# rev1.net
KiCad netlist of a schematic drawn in EAGLE
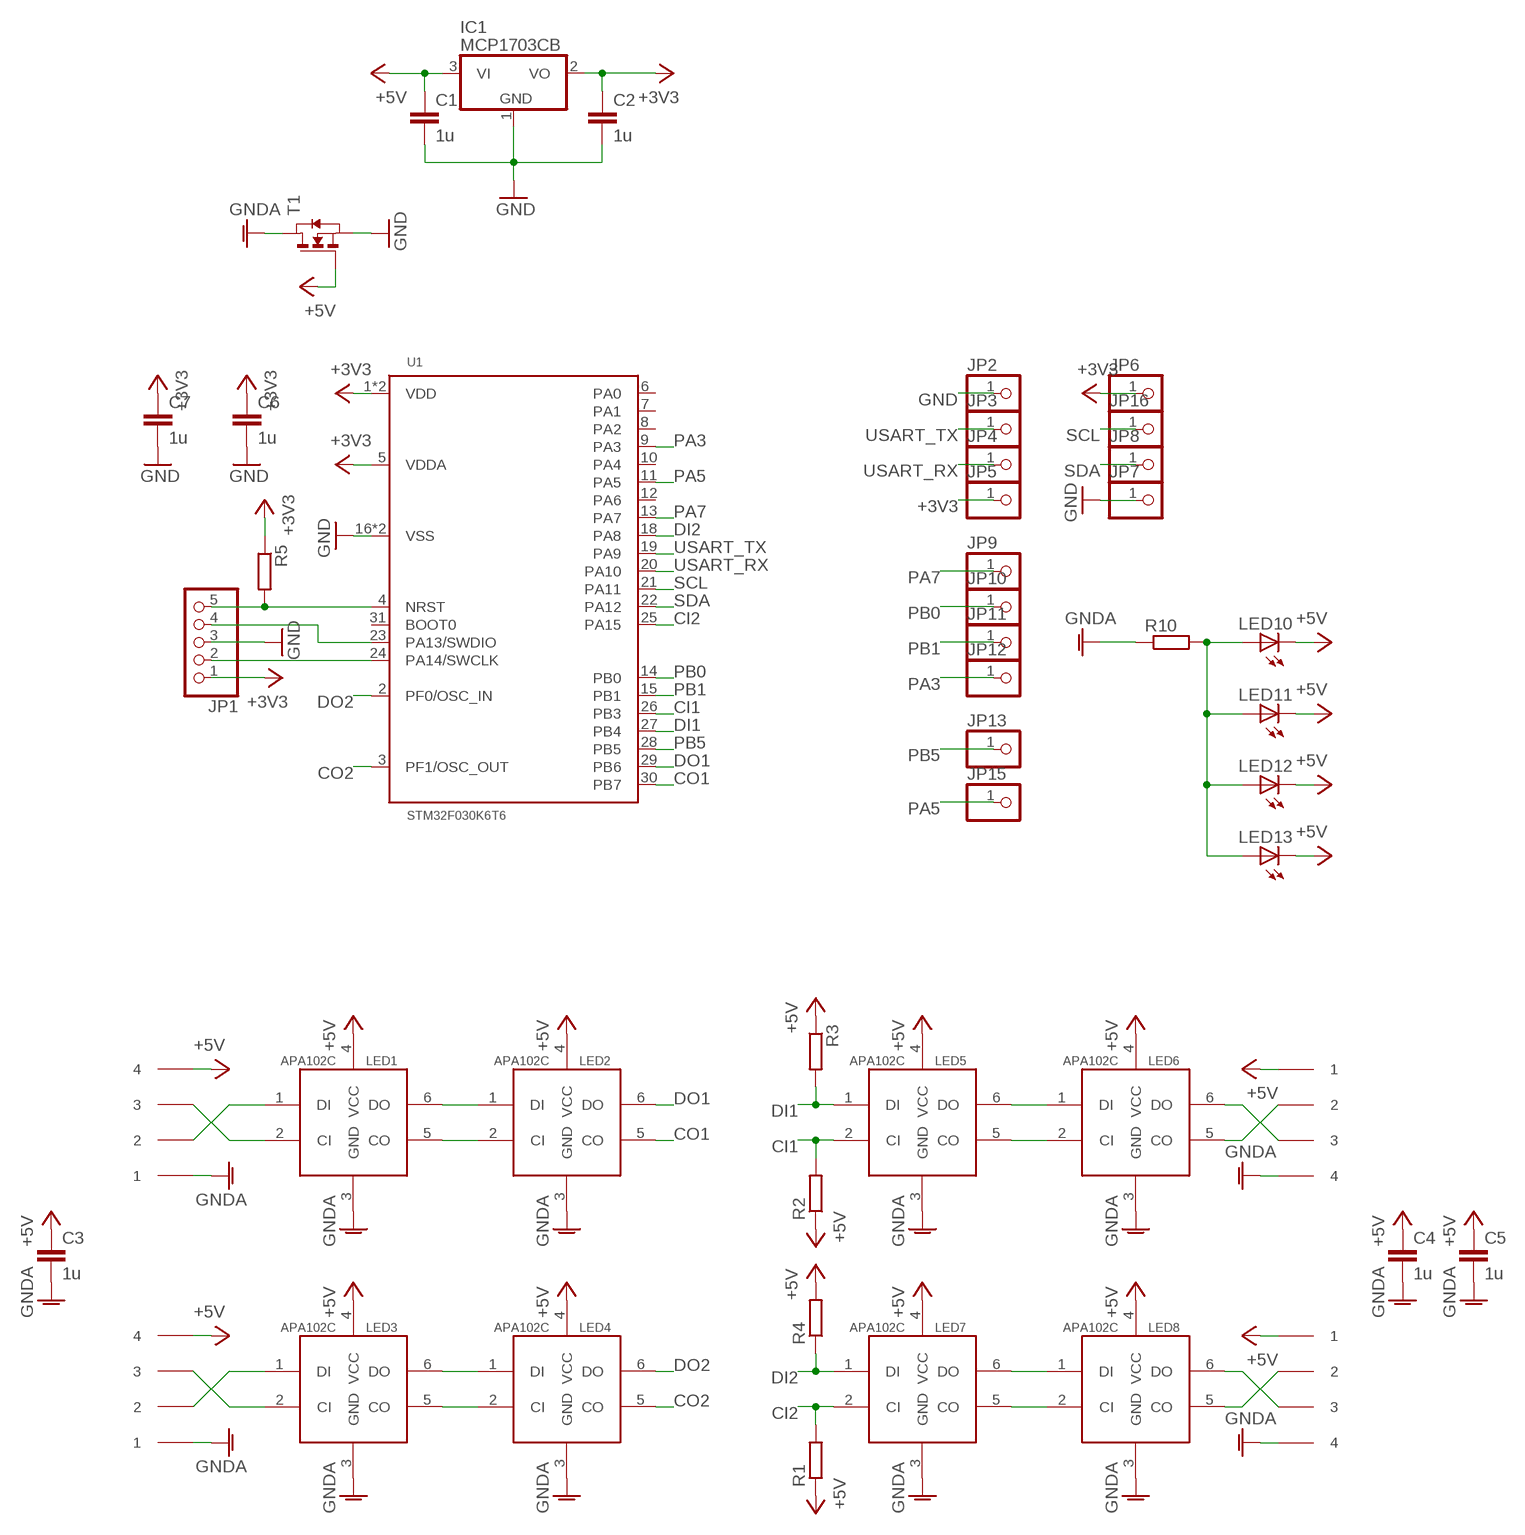
[diagram p0: schematic, sheet 1]

(export (version "E")
  (design (tool "Eeschema 10.0.6"))
  (components
    (comp (ref "C1")
      (value "1u")
      (footprint "eagle-import:C0603")
      (libsource (lib "eagle-import") (part "CC0603"))
    )
    (comp (ref "C2")
      (value "1u")
      (footprint "eagle-import:C0603")
      (libsource (lib "eagle-import") (part "CC0603"))
    )
    (comp (ref "C3")
      (value "1u")
      (footprint "eagle-import:C0603")
      (libsource (lib "eagle-import") (part "CC0603"))
    )
    (comp (ref "C4")
      (value "1u")
      (footprint "eagle-import:C0603")
      (libsource (lib "eagle-import") (part "CC0603"))
    )
    (comp (ref "C5")
      (value "1u")
      (footprint "eagle-import:C0603")
      (libsource (lib "eagle-import") (part "CC0603"))
    )
    (comp (ref "C6")
      (value "1u")
      (footprint "eagle-import:C0603")
      (libsource (lib "eagle-import") (part "CC0603"))
    )
    (comp (ref "C7")
      (value "1u")
      (footprint "eagle-import:C0603")
      (libsource (lib "eagle-import") (part "CC0603"))
    )
    (comp (ref "IC1")
      (value "MCP1703CB")
      (footprint "eagle-import:SOT23")
      (libsource (lib "eagle-import") (part "MCP1703CB"))
    )
    (comp (ref "JP1")
      (value "PINHD-1X5")
      (footprint "eagle-import:1X05")
      (libsource (lib "eagle-import") (part "PINHD-1X5"))
    )
    (comp (ref "JP2")
      (value "PINHD-1X1")
      (footprint "eagle-import:1X01")
      (libsource (lib "eagle-import") (part "PINHD-1X1"))
    )
    (comp (ref "JP3")
      (value "PINHD-1X1")
      (footprint "eagle-import:1X01")
      (libsource (lib "eagle-import") (part "PINHD-1X1"))
    )
    (comp (ref "JP4")
      (value "PINHD-1X1")
      (footprint "eagle-import:1X01")
      (libsource (lib "eagle-import") (part "PINHD-1X1"))
    )
    (comp (ref "JP5")
      (value "PINHD-1X1")
      (footprint "eagle-import:1X01")
      (libsource (lib "eagle-import") (part "PINHD-1X1"))
    )
    (comp (ref "JP6")
      (value "PINHD-1X1")
      (footprint "eagle-import:1X01")
      (libsource (lib "eagle-import") (part "PINHD-1X1"))
    )
    (comp (ref "JP7")
      (value "PINHD-1X1")
      (footprint "eagle-import:1X01")
      (libsource (lib "eagle-import") (part "PINHD-1X1"))
    )
    (comp (ref "JP8")
      (value "PINHD-1X1")
      (footprint "eagle-import:1X01")
      (libsource (lib "eagle-import") (part "PINHD-1X1"))
    )
    (comp (ref "JP9")
      (value "PINHD-1X1")
      (footprint "eagle-import:1X01")
      (libsource (lib "eagle-import") (part "PINHD-1X1"))
    )
    (comp (ref "JP10")
      (value "PINHD-1X1")
      (footprint "eagle-import:1X01")
      (libsource (lib "eagle-import") (part "PINHD-1X1"))
    )
    (comp (ref "JP11")
      (value "PINHD-1X1")
      (footprint "eagle-import:1X01")
      (libsource (lib "eagle-import") (part "PINHD-1X1"))
    )
    (comp (ref "JP12")
      (value "PINHD-1X1")
      (footprint "eagle-import:1X01")
      (libsource (lib "eagle-import") (part "PINHD-1X1"))
    )
    (comp (ref "JP13")
      (value "PINHD-1X1")
      (footprint "eagle-import:1X01")
      (libsource (lib "eagle-import") (part "PINHD-1X1"))
    )
    (comp (ref "JP15")
      (value "PINHD-1X1")
      (footprint "eagle-import:1X01")
      (libsource (lib "eagle-import") (part "PINHD-1X1"))
    )
    (comp (ref "JP16")
      (value "PINHD-1X1")
      (footprint "eagle-import:1X01")
      (libsource (lib "eagle-import") (part "PINHD-1X1"))
    )
    (comp (ref "LED1")
      (value "APA102C")
      (footprint "eagle-import:RGBLED5050")
      (libsource (lib "eagle-import") (part "APA102C"))
    )
    (comp (ref "LED2")
      (value "APA102C")
      (footprint "eagle-import:RGBLED5050")
      (libsource (lib "eagle-import") (part "APA102C"))
    )
    (comp (ref "LED3")
      (value "APA102C")
      (footprint "eagle-import:RGBLED5050")
      (libsource (lib "eagle-import") (part "APA102C"))
    )
    (comp (ref "LED4")
      (value "APA102C")
      (footprint "eagle-import:RGBLED5050")
      (libsource (lib "eagle-import") (part "APA102C"))
    )
    (comp (ref "LED5")
      (value "APA102C")
      (footprint "eagle-import:RGBLED5050")
      (libsource (lib "eagle-import") (part "APA102C"))
    )
    (comp (ref "LED6")
      (value "APA102C")
      (footprint "eagle-import:RGBLED5050")
      (libsource (lib "eagle-import") (part "APA102C"))
    )
    (comp (ref "LED7")
      (value "APA102C")
      (footprint "eagle-import:RGBLED5050")
      (libsource (lib "eagle-import") (part "APA102C"))
    )
    (comp (ref "LED8")
      (value "APA102C")
      (footprint "eagle-import:RGBLED5050")
      (libsource (lib "eagle-import") (part "APA102C"))
    )
    (comp (ref "LED10")
      (value "LEDSML0603")
      (footprint "eagle-import:SML0603")
      (libsource (lib "eagle-import") (part "LEDSML0603"))
    )
    (comp (ref "LED11")
      (value "LEDSML0603")
      (footprint "eagle-import:SML0603")
      (libsource (lib "eagle-import") (part "LEDSML0603"))
    )
    (comp (ref "LED12")
      (value "LEDSML0603")
      (footprint "eagle-import:SML0603")
      (libsource (lib "eagle-import") (part "LEDSML0603"))
    )
    (comp (ref "LED13")
      (value "LEDSML0603")
      (footprint "eagle-import:SML0603")
      (libsource (lib "eagle-import") (part "LEDSML0603"))
    )
    (comp (ref "R1")
      (value "RR0603")
      (footprint "eagle-import:R0603")
      (libsource (lib "eagle-import") (part "RR0603"))
    )
    (comp (ref "R2")
      (value "RR0603")
      (footprint "eagle-import:R0603")
      (libsource (lib "eagle-import") (part "RR0603"))
    )
    (comp (ref "R3")
      (value "RR0603")
      (footprint "eagle-import:R0603")
      (libsource (lib "eagle-import") (part "RR0603"))
    )
    (comp (ref "R4")
      (value "RR0603")
      (footprint "eagle-import:R0603")
      (libsource (lib "eagle-import") (part "RR0603"))
    )
    (comp (ref "R5")
      (value "RR0603")
      (footprint "eagle-import:R0603")
      (libsource (lib "eagle-import") (part "RR0603"))
    )
    (comp (ref "R10")
      (value "RR0603")
      (footprint "eagle-import:R0603")
      (libsource (lib "eagle-import") (part "RR0603"))
    )
    (comp (ref "T1")
      (value "NMOSSOT23-6")
      (footprint "eagle-import:SOT23-6")
      (libsource (lib "eagle-import") (part "NMOSSOT23-6"))
    )
    (comp (ref "U$1")
      (value "JSTPH")
      (footprint "eagle-import:JSTPH")
      (libsource (lib "eagle-import") (part "JSTPH"))
    )
    (comp (ref "U$2")
      (value "JSTPH")
      (footprint "eagle-import:JSTPH")
      (libsource (lib "eagle-import") (part "JSTPH"))
    )
    (comp (ref "U$3")
      (value "JSTPH")
      (footprint "eagle-import:JSTPH")
      (libsource (lib "eagle-import") (part "JSTPH"))
    )
    (comp (ref "U$4")
      (value "JSTPH")
      (footprint "eagle-import:JSTPH")
      (libsource (lib "eagle-import") (part "JSTPH"))
    )
    (comp (ref "U1")
      (value "STM32F030K6T6")
      (footprint "eagle-import:LQFP-32")
      (libsource (lib "eagle-import") (part "STM32F030K6T6-LQFP-32"))
    )
  )
  (nets
    (net (code "1") (name "+3V3") (class "Default")
      (node (ref "C2") (pin "1") (pinfunction "1_1") (pintype "passive"))
      (node (ref "C6") (pin "1") (pinfunction "1_1") (pintype "passive"))
      (node (ref "C7") (pin "1") (pinfunction "1_1") (pintype "passive"))
      (node (ref "IC1") (pin "2") (pinfunction "VO_2") (pintype "passive"))
      (node (ref "JP1") (pin "1") (pinfunction "1_1") (pintype "passive"))
      (node (ref "JP5") (pin "1") (pinfunction "1_1") (pintype "passive"))
      (node (ref "JP6") (pin "1") (pinfunction "1_1") (pintype "passive"))
      (node (ref "R5") (pin "1") (pinfunction "1_1") (pintype "passive"))
      (node (ref "U1") (pin "1") (pinfunction "VDD_1") (pintype "bidirectional"))
      (node (ref "U1") (pin "17") (pinfunction "VDD_17") (pintype "bidirectional"))
      (node (ref "U1") (pin "5") (pinfunction "VDDA_5") (pintype "bidirectional"))
    )
    (net (code "2") (name "+5V") (class "Default")
      (node (ref "C1") (pin "1") (pinfunction "1_1") (pintype "passive"))
      (node (ref "C3") (pin "1") (pinfunction "1_1") (pintype "passive"))
      (node (ref "C4") (pin "1") (pinfunction "1_1") (pintype "passive"))
      (node (ref "C5") (pin "1") (pinfunction "1_1") (pintype "passive"))
      (node (ref "IC1") (pin "3") (pinfunction "VI_3") (pintype "input"))
      (node (ref "LED1") (pin "4") (pinfunction "VCC_4") (pintype "power_in"))
      (node (ref "LED10") (pin "C") (pinfunction "C_C") (pintype "passive"))
      (node (ref "LED11") (pin "C") (pinfunction "C_C") (pintype "passive"))
      (node (ref "LED12") (pin "C") (pinfunction "C_C") (pintype "passive"))
      (node (ref "LED13") (pin "C") (pinfunction "C_C") (pintype "passive"))
      (node (ref "LED2") (pin "4") (pinfunction "VCC_4") (pintype "power_in"))
      (node (ref "LED3") (pin "4") (pinfunction "VCC_4") (pintype "power_in"))
      (node (ref "LED4") (pin "4") (pinfunction "VCC_4") (pintype "power_in"))
      (node (ref "LED5") (pin "4") (pinfunction "VCC_4") (pintype "power_in"))
      (node (ref "LED6") (pin "4") (pinfunction "VCC_4") (pintype "power_in"))
      (node (ref "LED7") (pin "4") (pinfunction "VCC_4") (pintype "power_in"))
      (node (ref "LED8") (pin "4") (pinfunction "VCC_4") (pintype "power_in"))
      (node (ref "R1") (pin "1") (pinfunction "1_1") (pintype "passive"))
      (node (ref "R2") (pin "1") (pinfunction "1_1") (pintype "passive"))
      (node (ref "R3") (pin "1") (pinfunction "1_1") (pintype "passive"))
      (node (ref "R4") (pin "2") (pinfunction "2_2") (pintype "passive"))
      (node (ref "T1") (pin "3") (pinfunction "G_3") (pintype "passive"))
      (node (ref "U$1") (pin "P$4") (pinfunction "4_P$4") (pintype "bidirectional"))
      (node (ref "U$2") (pin "P$4") (pinfunction "4_P$4") (pintype "bidirectional"))
      (node (ref "U$3") (pin "1") (pinfunction "1_1") (pintype "bidirectional"))
      (node (ref "U$4") (pin "1") (pinfunction "1_1") (pintype "bidirectional"))
    )
    (net (code "3") (name "/CI1") (class "Default")
      (node (ref "LED5") (pin "2") (pinfunction "CI_2") (pintype "input"))
      (node (ref "R2") (pin "2") (pinfunction "2_2") (pintype "passive"))
      (node (ref "U1") (pin "26") (pinfunction "PB3_26") (pintype "bidirectional"))
    )
    (net (code "4") (name "/CI2") (class "Default")
      (node (ref "LED7") (pin "2") (pinfunction "CI_2") (pintype "input"))
      (node (ref "R1") (pin "2") (pinfunction "2_2") (pintype "passive"))
      (node (ref "U1") (pin "25") (pinfunction "PA15_25") (pintype "bidirectional"))
    )
    (net (code "5") (name "/CO1") (class "Default")
      (node (ref "LED2") (pin "5") (pinfunction "CO_5") (pintype "output"))
      (node (ref "U1") (pin "30") (pinfunction "PB7_30") (pintype "bidirectional"))
    )
    (net (code "6") (name "/CO2") (class "Default")
      (node (ref "LED4") (pin "5") (pinfunction "CO_5") (pintype "output"))
      (node (ref "U1") (pin "3") (pinfunction "PF1/OSC_OUT_3") (pintype "bidirectional"))
    )
    (net (code "7") (name "/DI1") (class "Default")
      (node (ref "LED5") (pin "1") (pinfunction "DI_1") (pintype "input"))
      (node (ref "R3") (pin "2") (pinfunction "2_2") (pintype "passive"))
      (node (ref "U1") (pin "27") (pinfunction "PB4_27") (pintype "bidirectional"))
    )
    (net (code "8") (name "/DI2") (class "Default")
      (node (ref "LED7") (pin "1") (pinfunction "DI_1") (pintype "input"))
      (node (ref "R4") (pin "1") (pinfunction "1_1") (pintype "passive"))
      (node (ref "U1") (pin "18") (pinfunction "PA8_18") (pintype "bidirectional"))
    )
    (net (code "9") (name "/DO1") (class "Default")
      (node (ref "LED2") (pin "6") (pinfunction "DO_6") (pintype "output"))
      (node (ref "U1") (pin "29") (pinfunction "PB6_29") (pintype "bidirectional"))
    )
    (net (code "10") (name "/DO2") (class "Default")
      (node (ref "LED4") (pin "6") (pinfunction "DO_6") (pintype "output"))
      (node (ref "U1") (pin "2") (pinfunction "PF0/OSC_IN_2") (pintype "bidirectional"))
    )
    (net (code "11") (name "/PA3") (class "Default")
      (node (ref "JP12") (pin "1") (pinfunction "1_1") (pintype "passive"))
      (node (ref "U1") (pin "9") (pinfunction "PA3_9") (pintype "bidirectional"))
    )
    (net (code "12") (name "/PA5") (class "Default")
      (node (ref "JP15") (pin "1") (pinfunction "1_1") (pintype "passive"))
      (node (ref "U1") (pin "11") (pinfunction "PA5_11") (pintype "bidirectional"))
    )
    (net (code "13") (name "/PA7") (class "Default")
      (node (ref "JP9") (pin "1") (pinfunction "1_1") (pintype "passive"))
      (node (ref "U1") (pin "13") (pinfunction "PA7_13") (pintype "bidirectional"))
    )
    (net (code "14") (name "/PB0") (class "Default")
      (node (ref "JP10") (pin "1") (pinfunction "1_1") (pintype "passive"))
      (node (ref "U1") (pin "14") (pinfunction "PB0_14") (pintype "bidirectional"))
    )
    (net (code "15") (name "/PB1") (class "Default")
      (node (ref "JP11") (pin "1") (pinfunction "1_1") (pintype "passive"))
      (node (ref "U1") (pin "15") (pinfunction "PB1_15") (pintype "bidirectional"))
    )
    (net (code "16") (name "/PB5") (class "Default")
      (node (ref "JP13") (pin "1") (pinfunction "1_1") (pintype "passive"))
      (node (ref "U1") (pin "28") (pinfunction "PB5_28") (pintype "bidirectional"))
    )
    (net (code "17") (name "/SCL") (class "Default")
      (node (ref "JP16") (pin "1") (pinfunction "1_1") (pintype "passive"))
      (node (ref "U1") (pin "21") (pinfunction "PA11_21") (pintype "bidirectional"))
    )
    (net (code "18") (name "/SDA") (class "Default")
      (node (ref "JP8") (pin "1") (pinfunction "1_1") (pintype "passive"))
      (node (ref "U1") (pin "22") (pinfunction "PA12_22") (pintype "bidirectional"))
    )
    (net (code "19") (name "/USART_RX") (class "Default")
      (node (ref "JP4") (pin "1") (pinfunction "1_1") (pintype "passive"))
      (node (ref "U1") (pin "20") (pinfunction "PA10_20") (pintype "bidirectional"))
    )
    (net (code "20") (name "/USART_TX") (class "Default")
      (node (ref "JP3") (pin "1") (pinfunction "1_1") (pintype "passive"))
      (node (ref "U1") (pin "19") (pinfunction "PA9_19") (pintype "bidirectional"))
    )
    (net (code "21") (name "GND") (class "Default")
      (node (ref "C1") (pin "2") (pinfunction "2_2") (pintype "passive"))
      (node (ref "C2") (pin "2") (pinfunction "2_2") (pintype "passive"))
      (node (ref "C6") (pin "2") (pinfunction "2_2") (pintype "passive"))
      (node (ref "C7") (pin "2") (pinfunction "2_2") (pintype "passive"))
      (node (ref "IC1") (pin "1") (pinfunction "GND_1") (pintype "passive"))
      (node (ref "JP1") (pin "3") (pinfunction "3_3") (pintype "passive"))
      (node (ref "JP2") (pin "1") (pinfunction "1_1") (pintype "passive"))
      (node (ref "JP7") (pin "1") (pinfunction "1_1") (pintype "passive"))
      (node (ref "T1") (pin "4") (pinfunction "S_4") (pintype "passive"))
      (node (ref "U1") (pin "16") (pinfunction "VSS_16") (pintype "bidirectional"))
      (node (ref "U1") (pin "32") (pinfunction "VSS_32") (pintype "bidirectional"))
    )
    (net (code "22") (name "GNDA") (class "Default")
      (node (ref "C3") (pin "2") (pinfunction "2_2") (pintype "passive"))
      (node (ref "C4") (pin "2") (pinfunction "2_2") (pintype "passive"))
      (node (ref "C5") (pin "2") (pinfunction "2_2") (pintype "passive"))
      (node (ref "LED1") (pin "3") (pinfunction "GND_3") (pintype "power_in"))
      (node (ref "LED2") (pin "3") (pinfunction "GND_3") (pintype "power_in"))
      (node (ref "LED3") (pin "3") (pinfunction "GND_3") (pintype "power_in"))
      (node (ref "LED4") (pin "3") (pinfunction "GND_3") (pintype "power_in"))
      (node (ref "LED5") (pin "3") (pinfunction "GND_3") (pintype "power_in"))
      (node (ref "LED6") (pin "3") (pinfunction "GND_3") (pintype "power_in"))
      (node (ref "LED7") (pin "3") (pinfunction "GND_3") (pintype "power_in"))
      (node (ref "LED8") (pin "3") (pinfunction "GND_3") (pintype "power_in"))
      (node (ref "R10") (pin "1") (pinfunction "1_1") (pintype "passive"))
      (node (ref "T1") (pin "1") (pinfunction "D_1") (pintype "passive"))
      (node (ref "T1") (pin "2") (pinfunction "D_2") (pintype "passive"))
      (node (ref "T1") (pin "5") (pinfunction "D_5") (pintype "passive"))
      (node (ref "T1") (pin "6") (pinfunction "D_6") (pintype "passive"))
      (node (ref "U$1") (pin "1") (pinfunction "1_1") (pintype "bidirectional"))
      (node (ref "U$2") (pin "1") (pinfunction "1_1") (pintype "bidirectional"))
      (node (ref "U$3") (pin "P$4") (pinfunction "4_P$4") (pintype "bidirectional"))
      (node (ref "U$4") (pin "P$4") (pinfunction "4_P$4") (pintype "bidirectional"))
    )
    (net (code "23") (name "Net-(LED1-CI)") (class "Default")
      (node (ref "LED1") (pin "2") (pinfunction "CI_2") (pintype "input"))
      (node (ref "U$1") (pin "P$3") (pinfunction "3_P$3") (pintype "bidirectional"))
    )
    (net (code "24") (name "Net-(LED1-CO)") (class "Default")
      (node (ref "LED1") (pin "5") (pinfunction "CO_5") (pintype "output"))
      (node (ref "LED2") (pin "2") (pinfunction "CI_2") (pintype "input"))
    )
    (net (code "25") (name "Net-(LED1-DI)") (class "Default")
      (node (ref "LED1") (pin "1") (pinfunction "DI_1") (pintype "input"))
      (node (ref "U$1") (pin "P$2") (pinfunction "2_P$2") (pintype "bidirectional"))
    )
    (net (code "26") (name "Net-(LED1-DO)") (class "Default")
      (node (ref "LED1") (pin "6") (pinfunction "DO_6") (pintype "output"))
      (node (ref "LED2") (pin "1") (pinfunction "DI_1") (pintype "input"))
    )
    (net (code "27") (name "Net-(LED3-CI)") (class "Default")
      (node (ref "LED3") (pin "2") (pinfunction "CI_2") (pintype "input"))
      (node (ref "U$2") (pin "P$3") (pinfunction "3_P$3") (pintype "bidirectional"))
    )
    (net (code "28") (name "Net-(LED3-CO)") (class "Default")
      (node (ref "LED3") (pin "5") (pinfunction "CO_5") (pintype "output"))
      (node (ref "LED4") (pin "2") (pinfunction "CI_2") (pintype "input"))
    )
    (net (code "29") (name "Net-(LED3-DI)") (class "Default")
      (node (ref "LED3") (pin "1") (pinfunction "DI_1") (pintype "input"))
      (node (ref "U$2") (pin "P$2") (pinfunction "2_P$2") (pintype "bidirectional"))
    )
    (net (code "30") (name "Net-(LED3-DO)") (class "Default")
      (node (ref "LED3") (pin "6") (pinfunction "DO_6") (pintype "output"))
      (node (ref "LED4") (pin "1") (pinfunction "DI_1") (pintype "input"))
    )
    (net (code "31") (name "Net-(LED5-CO)") (class "Default")
      (node (ref "LED5") (pin "5") (pinfunction "CO_5") (pintype "output"))
      (node (ref "LED6") (pin "2") (pinfunction "CI_2") (pintype "input"))
    )
    (net (code "32") (name "Net-(LED5-DO)") (class "Default")
      (node (ref "LED5") (pin "6") (pinfunction "DO_6") (pintype "output"))
      (node (ref "LED6") (pin "1") (pinfunction "DI_1") (pintype "input"))
    )
    (net (code "33") (name "Net-(LED6-CO)") (class "Default")
      (node (ref "LED6") (pin "5") (pinfunction "CO_5") (pintype "output"))
      (node (ref "U$4") (pin "P$2") (pinfunction "2_P$2") (pintype "bidirectional"))
    )
    (net (code "34") (name "Net-(LED6-DO)") (class "Default")
      (node (ref "LED6") (pin "6") (pinfunction "DO_6") (pintype "output"))
      (node (ref "U$4") (pin "P$3") (pinfunction "3_P$3") (pintype "bidirectional"))
    )
    (net (code "35") (name "Net-(LED7-CO)") (class "Default")
      (node (ref "LED7") (pin "5") (pinfunction "CO_5") (pintype "output"))
      (node (ref "LED8") (pin "2") (pinfunction "CI_2") (pintype "input"))
    )
    (net (code "36") (name "Net-(LED7-DO)") (class "Default")
      (node (ref "LED7") (pin "6") (pinfunction "DO_6") (pintype "output"))
      (node (ref "LED8") (pin "1") (pinfunction "DI_1") (pintype "input"))
    )
    (net (code "37") (name "Net-(LED8-CO)") (class "Default")
      (node (ref "LED8") (pin "5") (pinfunction "CO_5") (pintype "output"))
      (node (ref "U$3") (pin "P$2") (pinfunction "2_P$2") (pintype "bidirectional"))
    )
    (net (code "38") (name "Net-(LED8-DO)") (class "Default")
      (node (ref "LED8") (pin "6") (pinfunction "DO_6") (pintype "output"))
      (node (ref "U$3") (pin "P$3") (pinfunction "3_P$3") (pintype "bidirectional"))
    )
    (net (code "39") (name "Net-(LED10-PadA)") (class "Default")
      (node (ref "LED10") (pin "A") (pinfunction "A_A") (pintype "passive"))
      (node (ref "LED11") (pin "A") (pinfunction "A_A") (pintype "passive"))
      (node (ref "LED12") (pin "A") (pinfunction "A_A") (pintype "passive"))
      (node (ref "LED13") (pin "A") (pinfunction "A_A") (pintype "passive"))
      (node (ref "R10") (pin "2") (pinfunction "2_2") (pintype "passive"))
    )
    (net (code "40") (name "Net-(U1-NRST)") (class "Default")
      (node (ref "JP1") (pin "5") (pinfunction "5_5") (pintype "passive"))
      (node (ref "R5") (pin "2") (pinfunction "2_2") (pintype "passive"))
      (node (ref "U1") (pin "4") (pinfunction "NRST_4") (pintype "bidirectional"))
    )
    (net (code "41") (name "Net-(U1-PA13{slash}SWDIO)") (class "Default")
      (node (ref "JP1") (pin "4") (pinfunction "4_4") (pintype "passive"))
      (node (ref "U1") (pin "23") (pinfunction "PA13/SWDIO_23") (pintype "bidirectional"))
    )
    (net (code "42") (name "Net-(U1-PA14{slash}SWCLK)") (class "Default")
      (node (ref "JP1") (pin "2") (pinfunction "2_2") (pintype "passive"))
      (node (ref "U1") (pin "24") (pinfunction "PA14/SWCLK_24") (pintype "bidirectional"))
    )
    (net (code "43") (name "unconnected-(U1-BOOT0-Pad31)") (class "Default")
      (node (ref "U1") (pin "31") (pinfunction "BOOT0_31") (pintype "bidirectional"))
    )
    (net (code "44") (name "unconnected-(U1-PA0-Pad6)") (class "Default")
      (node (ref "U1") (pin "6") (pinfunction "PA0_6") (pintype "bidirectional"))
    )
    (net (code "45") (name "unconnected-(U1-PA1-Pad7)") (class "Default")
      (node (ref "U1") (pin "7") (pinfunction "PA1_7") (pintype "bidirectional"))
    )
    (net (code "46") (name "unconnected-(U1-PA2-Pad8)") (class "Default")
      (node (ref "U1") (pin "8") (pinfunction "PA2_8") (pintype "bidirectional"))
    )
    (net (code "47") (name "unconnected-(U1-PA4-Pad10)") (class "Default")
      (node (ref "U1") (pin "10") (pinfunction "PA4_10") (pintype "bidirectional"))
    )
    (net (code "48") (name "unconnected-(U1-PA6-Pad12)") (class "Default")
      (node (ref "U1") (pin "12") (pinfunction "PA6_12") (pintype "bidirectional"))
    )
  )
)
